# RC-SD2IEC_DJV.net
KiCad netlist of a schematic drawn in EAGLE
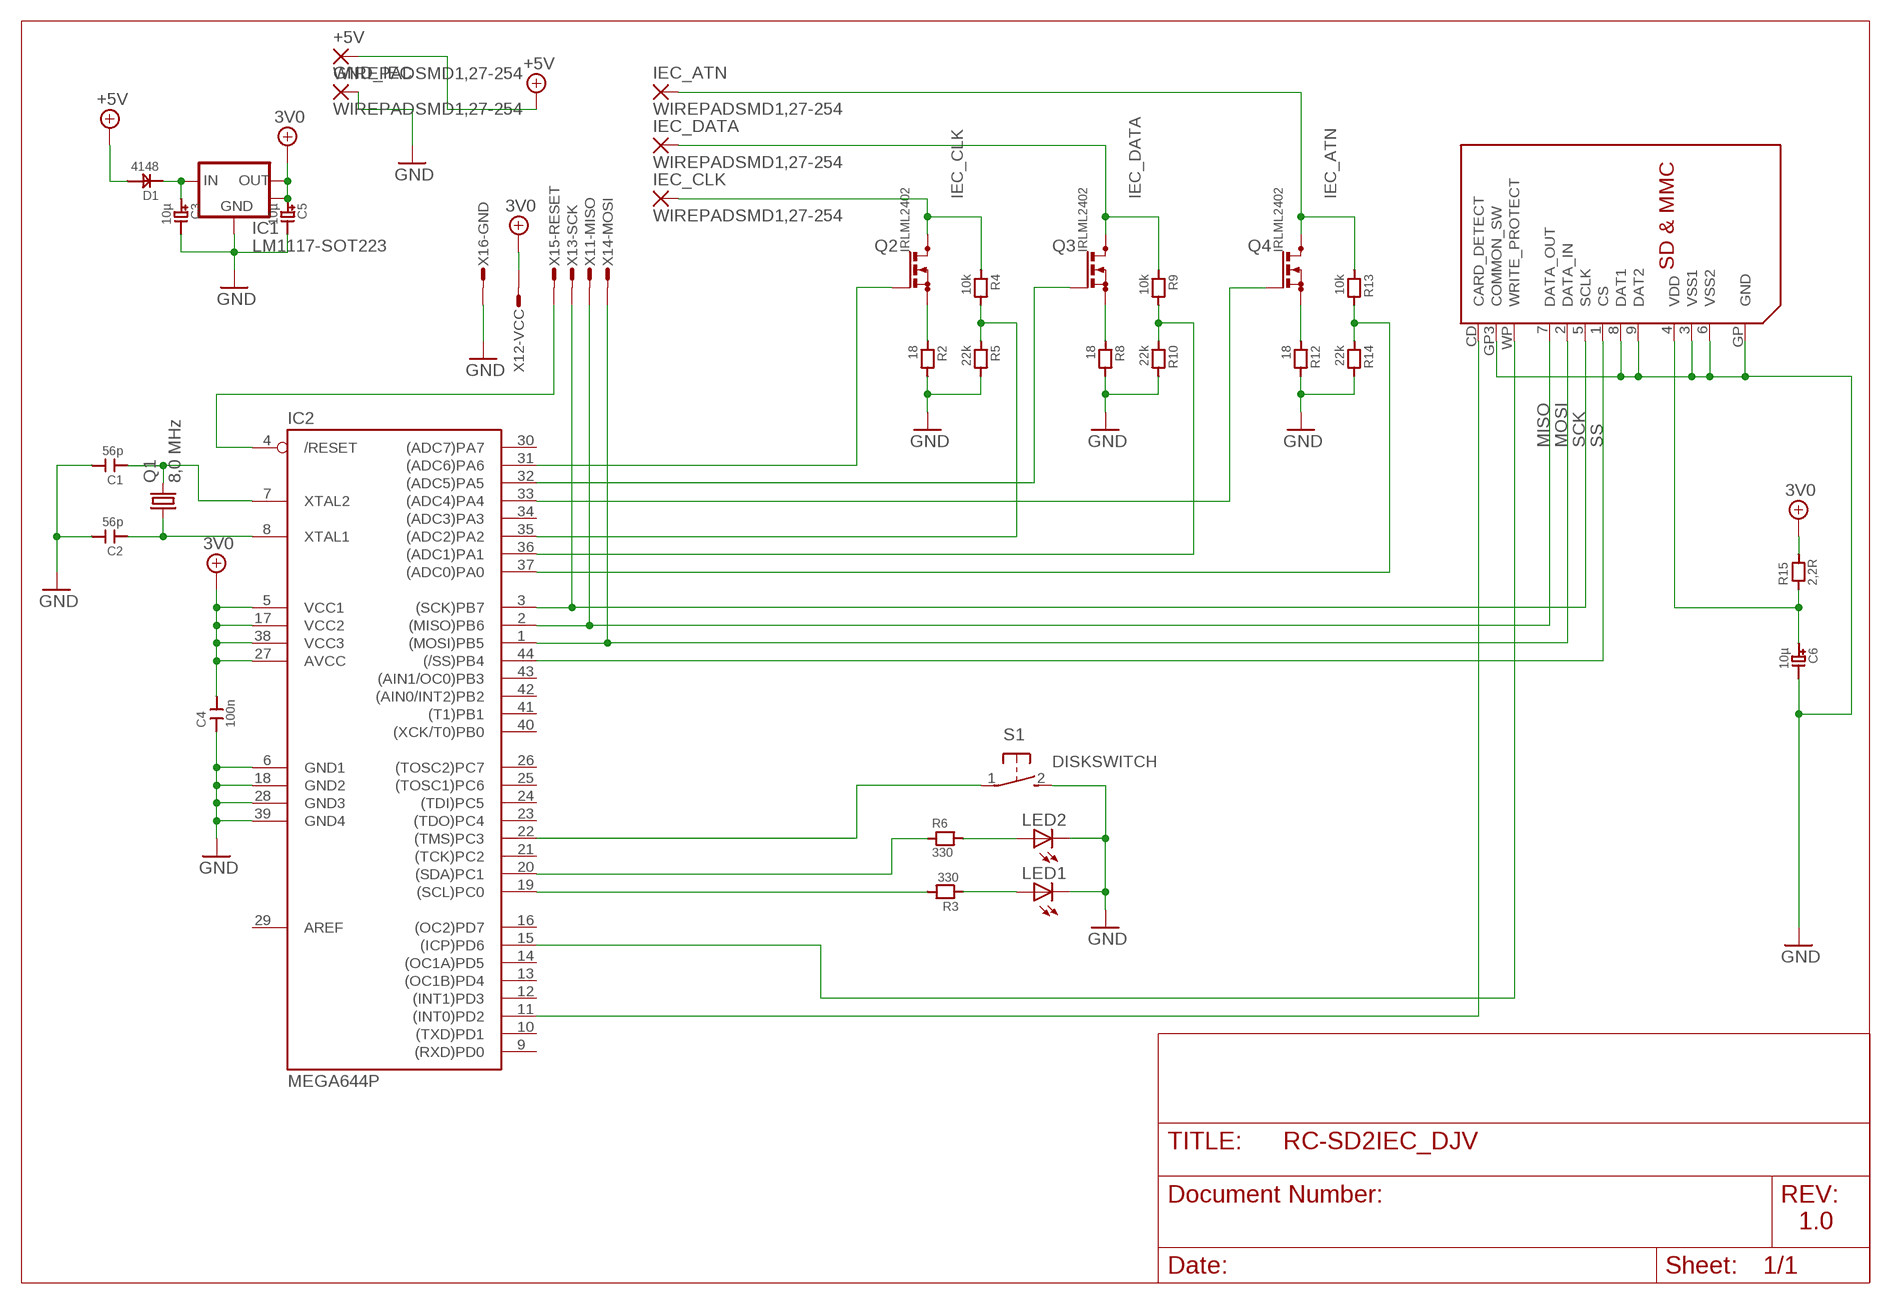
[diagram p0: schematic, sheet 1]

(export (version "E")
  (design (tool "Eeschema 10.0.6"))
  (components
    (comp (ref "+5V")
      (value "WIREPADSMD1,27-254")
      (footprint "eagle-import:SMD1,27-2,54")
      (libsource (lib "eagle-import") (part "WIREPADSMD1,27-254"))
    )
    (comp (ref "C1")
      (value "56p")
      (footprint "eagle-import:C0805")
      (libsource (lib "eagle-import") (part "C0805"))
    )
    (comp (ref "C2")
      (value "56p")
      (footprint "eagle-import:C0805")
      (libsource (lib "eagle-import") (part "C0805"))
    )
    (comp (ref "C3")
      (value "10µ")
      (footprint "eagle-import:C_TANTAL_A")
      (libsource (lib "eagle-import") (part "C_POLTA_A"))
    )
    (comp (ref "C4")
      (value "100n")
      (footprint "eagle-import:C1206")
      (libsource (lib "eagle-import") (part "C1206"))
    )
    (comp (ref "C5")
      (value "10µ")
      (footprint "eagle-import:C_TANTAL_A")
      (libsource (lib "eagle-import") (part "C_POLTA_A"))
    )
    (comp (ref "C6")
      (value "10µ")
      (footprint "eagle-import:C_TANTAL_A")
      (libsource (lib "eagle-import") (part "C_POLTA_A"))
    )
    (comp (ref "D1")
      (value "4148")
      (footprint "eagle-import:SOD-123")
      (libsource (lib "eagle-import") (part "DSOD-123"))
    )
    (comp (ref "GND_IEC")
      (value "WIREPADSMD1,27-254")
      (footprint "eagle-import:SMD1,27-2,54")
      (libsource (lib "eagle-import") (part "WIREPADSMD1,27-254"))
    )
    (comp (ref "IC1")
      (value "LM1117-SOT223")
      (footprint "eagle-import:SOT-223-3")
      (libsource (lib "eagle-import") (part "LM1117-SOT223"))
    )
    (comp (ref "IC2")
      (value "MEGA644P")
      (footprint "eagle-import:TQFP44")
      (libsource (lib "eagle-import") (part "MEGA16/32TQFP"))
    )
    (comp (ref "IEC_ATN")
      (value "WIREPADSMD1,27-254")
      (footprint "eagle-import:SMD1,27-2,54")
      (libsource (lib "eagle-import") (part "WIREPADSMD1,27-254"))
    )
    (comp (ref "IEC_CLK")
      (value "WIREPADSMD1,27-254")
      (footprint "eagle-import:SMD1,27-2,54")
      (libsource (lib "eagle-import") (part "WIREPADSMD1,27-254"))
    )
    (comp (ref "IEC_DATA")
      (value "WIREPADSMD1,27-254")
      (footprint "eagle-import:SMD1,27-2,54")
      (libsource (lib "eagle-import") (part "WIREPADSMD1,27-254"))
    )
    (comp (ref "LED1")
      (value "LED3MM")
      (footprint "eagle-import:LED3MM")
      (libsource (lib "eagle-import") (part "LED3MM"))
    )
    (comp (ref "LED2")
      (value "LED3MM")
      (footprint "eagle-import:LED3MM")
      (libsource (lib "eagle-import") (part "LED3MM"))
    )
    (comp (ref "Q1")
      (value "8,0 MHz")
      (footprint "eagle-import:CTS406")
      (libsource (lib "eagle-import") (part "CRYSTALCTS406"))
    )
    (comp (ref "Q2")
      (value "IRLML2402")
      (footprint "eagle-import:SOT23_C")
      (libsource (lib "eagle-import") (part "BSN20_C"))
    )
    (comp (ref "Q3")
      (value "IRLML2402")
      (footprint "eagle-import:SOT23_C")
      (libsource (lib "eagle-import") (part "BSN20_C"))
    )
    (comp (ref "Q4")
      (value "IRLML2402")
      (footprint "eagle-import:SOT23_C")
      (libsource (lib "eagle-import") (part "BSN20_C"))
    )
    (comp (ref "R2")
      (value "18")
      (footprint "eagle-import:R0805")
      (libsource (lib "eagle-import") (part "R0805"))
    )
    (comp (ref "R3")
      (value "330")
      (footprint "eagle-import:R0805")
      (libsource (lib "eagle-import") (part "R0805"))
    )
    (comp (ref "R4")
      (value "10k")
      (footprint "eagle-import:R0805")
      (libsource (lib "eagle-import") (part "R0805"))
    )
    (comp (ref "R5")
      (value "22k")
      (footprint "eagle-import:R0805")
      (libsource (lib "eagle-import") (part "R0805"))
    )
    (comp (ref "R6")
      (value "330")
      (footprint "eagle-import:R0805")
      (libsource (lib "eagle-import") (part "R0805"))
    )
    (comp (ref "R8")
      (value "18")
      (footprint "eagle-import:R0805")
      (libsource (lib "eagle-import") (part "R0805"))
    )
    (comp (ref "R9")
      (value "10k")
      (footprint "eagle-import:R0805")
      (libsource (lib "eagle-import") (part "R0805"))
    )
    (comp (ref "R10")
      (value "22k")
      (footprint "eagle-import:R0805")
      (libsource (lib "eagle-import") (part "R0805"))
    )
    (comp (ref "R12")
      (value "18")
      (footprint "eagle-import:R0805")
      (libsource (lib "eagle-import") (part "R0805"))
    )
    (comp (ref "R13")
      (value "10k")
      (footprint "eagle-import:R0805")
      (libsource (lib "eagle-import") (part "R0805"))
    )
    (comp (ref "R14")
      (value "22k")
      (footprint "eagle-import:R0805")
      (libsource (lib "eagle-import") (part "R0805"))
    )
    (comp (ref "R15")
      (value "2,2R")
      (footprint "eagle-import:R0805")
      (libsource (lib "eagle-import") (part "R0805"))
    )
    (comp (ref "S1")
      (value "31-XX")
      (footprint "eagle-import:B3F-31XX")
      (libsource (lib "eagle-import") (part "31-XX"))
    )
    (comp (ref "SDMMC1")
      (value "SDMMC06132")
      (footprint "eagle-import:06132")
      (libsource (lib "eagle-import") (part "SDMMC06132"))
    )
    (comp (ref "X1")
      (value "AVR-ISP_1X6")
      (footprint "eagle-import:1X6_ISP")
      (libsource (lib "eagle-import") (part "AVR-ISP_1X6"))
    )
  )
  (nets
    (net (code "1") (name "+5V") (class "Default")
      (node (ref "+5V") (pin "1") (pinfunction "P_1") (pintype "passive"))
      (node (ref "D1") (pin "2") (pinfunction "2_2") (pintype "passive"))
    )
    (net (code "2") (name "/DISKSWITCH") (class "Default")
      (node (ref "IC2") (pin "22") (pinfunction "(TMS)PC3_22") (pintype "bidirectional"))
      (node (ref "S1") (pin "1") (pinfunction "P_1") (pintype "passive"))
    )
    (net (code "3") (name "/IEC_ATN") (class "Default")
      (node (ref "IEC_ATN") (pin "1") (pinfunction "P_1") (pintype "passive"))
      (node (ref "Q4") (pin "3") (pinfunction "D_3") (pintype "passive"))
      (node (ref "R13") (pin "1") (pinfunction "1_1") (pintype "passive"))
    )
    (net (code "4") (name "/IEC_CLK") (class "Default")
      (node (ref "IEC_CLK") (pin "1") (pinfunction "P_1") (pintype "passive"))
      (node (ref "Q2") (pin "3") (pinfunction "D_3") (pintype "passive"))
      (node (ref "R4") (pin "1") (pinfunction "1_1") (pintype "passive"))
    )
    (net (code "5") (name "/IEC_DATA") (class "Default")
      (node (ref "IEC_DATA") (pin "1") (pinfunction "P_1") (pintype "passive"))
      (node (ref "Q3") (pin "3") (pinfunction "D_3") (pintype "passive"))
      (node (ref "R9") (pin "1") (pinfunction "1_1") (pintype "passive"))
    )
    (net (code "6") (name "/MISO") (class "Default")
      (node (ref "IC2") (pin "2") (pinfunction "(MISO)PB6_2") (pintype "bidirectional"))
      (node (ref "SDMMC1") (pin "7") (pinfunction "DATA_OUT_7") (pintype "output"))
      (node (ref "X1") (pin "1") (pinfunction "S_1") (pintype "passive"))
    )
    (net (code "7") (name "/MOSI") (class "Default")
      (node (ref "IC2") (pin "1") (pinfunction "(MOSI)PB5_1") (pintype "bidirectional"))
      (node (ref "SDMMC1") (pin "2") (pinfunction "DATA_IN_2") (pintype "input"))
      (node (ref "X1") (pin "4") (pinfunction "S_4") (pintype "passive"))
    )
    (net (code "8") (name "/SCK") (class "Default")
      (node (ref "IC2") (pin "3") (pinfunction "(SCK)PB7_3") (pintype "bidirectional"))
      (node (ref "SDMMC1") (pin "5") (pinfunction "SCLK_5") (pintype "input"))
      (node (ref "X1") (pin "3") (pinfunction "S_3") (pintype "passive"))
    )
    (net (code "9") (name "/SS") (class "Default")
      (node (ref "IC2") (pin "44") (pinfunction "(/SS)PB4_44") (pintype "bidirectional"))
      (node (ref "SDMMC1") (pin "1") (pinfunction "CS_1") (pintype "input"))
    )
    (net (code "10") (name "3V0") (class "Default")
      (node (ref "C4") (pin "2") (pinfunction "2_2") (pintype "passive"))
      (node (ref "C5") (pin "1") (pinfunction "1_1") (pintype "passive"))
      (node (ref "IC1") (pin "2") (pinfunction "VOUT_2") (pintype "bidirectional"))
      (node (ref "IC1") (pin "4") (pinfunction "HEATSINK_4") (pintype "bidirectional"))
      (node (ref "IC2") (pin "17") (pinfunction "VCC2_17") (pintype "power_in"))
      (node (ref "IC2") (pin "27") (pinfunction "AVCC_27") (pintype "power_in"))
      (node (ref "IC2") (pin "38") (pinfunction "VCC3_38") (pintype "power_in"))
      (node (ref "IC2") (pin "5") (pinfunction "VCC1_5") (pintype "power_in"))
      (node (ref "R15") (pin "2") (pinfunction "2_2") (pintype "passive"))
      (node (ref "X1") (pin "2") (pinfunction "S_2") (pintype "passive"))
    )
    (net (code "11") (name "GND") (class "Default")
      (node (ref "C1") (pin "2") (pinfunction "2_2") (pintype "passive"))
      (node (ref "C2") (pin "2") (pinfunction "2_2") (pintype "passive"))
      (node (ref "C3") (pin "2") (pinfunction "2_2") (pintype "passive"))
      (node (ref "C4") (pin "1") (pinfunction "1_1") (pintype "passive"))
      (node (ref "C5") (pin "2") (pinfunction "2_2") (pintype "passive"))
      (node (ref "C6") (pin "2") (pinfunction "2_2") (pintype "passive"))
      (node (ref "GND_IEC") (pin "1") (pinfunction "P_1") (pintype "passive"))
      (node (ref "IC1") (pin "1") (pinfunction "GND_1") (pintype "bidirectional"))
      (node (ref "IC2") (pin "18") (pinfunction "GND2_18") (pintype "power_in"))
      (node (ref "IC2") (pin "28") (pinfunction "GND3_28") (pintype "power_in"))
      (node (ref "IC2") (pin "39") (pinfunction "GND4_39") (pintype "power_in"))
      (node (ref "IC2") (pin "6") (pinfunction "GND1_6") (pintype "power_in"))
      (node (ref "LED1") (pin "K") (pinfunction "C_K") (pintype "passive"))
      (node (ref "LED2") (pin "K") (pinfunction "C_K") (pintype "passive"))
      (node (ref "R10") (pin "2") (pinfunction "2_2") (pintype "passive"))
      (node (ref "R12") (pin "2") (pinfunction "2_2") (pintype "passive"))
      (node (ref "R14") (pin "2") (pinfunction "2_2") (pintype "passive"))
      (node (ref "R2") (pin "2") (pinfunction "2_2") (pintype "passive"))
      (node (ref "R5") (pin "2") (pinfunction "2_2") (pintype "passive"))
      (node (ref "R8") (pin "2") (pinfunction "2_2") (pintype "passive"))
      (node (ref "S1") (pin "2") (pinfunction "S_2") (pintype "passive"))
      (node (ref "SDMMC1") (pin "3") (pinfunction "VSS1_3") (pintype "power_in"))
      (node (ref "SDMMC1") (pin "6") (pinfunction "VSS2_6") (pintype "power_in"))
      (node (ref "SDMMC1") (pin "8") (pinfunction "DAT1_8") (pintype "bidirectional"))
      (node (ref "SDMMC1") (pin "9") (pinfunction "DAT2_9") (pintype "bidirectional"))
      (node (ref "SDMMC1") (pin "GP") (pinfunction "GND_GP") (pintype "power_in"))
      (node (ref "SDMMC1") (pin "GP3") (pinfunction "COMMON_SW_GP3") (pintype "passive"))
      (node (ref "X1") (pin "6") (pinfunction "S_6") (pintype "passive"))
    )
    (net (code "12") (name "Net-(IC1-VIN)") (class "Default")
      (node (ref "C3") (pin "1") (pinfunction "1_1") (pintype "passive"))
      (node (ref "D1") (pin "1") (pinfunction "1_1") (pintype "passive"))
      (node (ref "IC1") (pin "3") (pinfunction "VIN_3") (pintype "bidirectional"))
    )
    (net (code "13") (name "Net-(IC2-(ADC0)PA0)") (class "Default")
      (node (ref "IC2") (pin "37") (pinfunction "(ADC0)PA0_37") (pintype "bidirectional"))
      (node (ref "R13") (pin "2") (pinfunction "2_2") (pintype "passive"))
      (node (ref "R14") (pin "1") (pinfunction "1_1") (pintype "passive"))
    )
    (net (code "14") (name "Net-(IC2-(ADC1)PA1)") (class "Default")
      (node (ref "IC2") (pin "36") (pinfunction "(ADC1)PA1_36") (pintype "bidirectional"))
      (node (ref "R10") (pin "1") (pinfunction "1_1") (pintype "passive"))
      (node (ref "R9") (pin "2") (pinfunction "2_2") (pintype "passive"))
    )
    (net (code "15") (name "Net-(IC2-(ADC2)PA2)") (class "Default")
      (node (ref "IC2") (pin "35") (pinfunction "(ADC2)PA2_35") (pintype "bidirectional"))
      (node (ref "R4") (pin "2") (pinfunction "2_2") (pintype "passive"))
      (node (ref "R5") (pin "1") (pinfunction "1_1") (pintype "passive"))
    )
    (net (code "16") (name "Net-(IC2-(ADC4)PA4)") (class "Default")
      (node (ref "IC2") (pin "33") (pinfunction "(ADC4)PA4_33") (pintype "bidirectional"))
      (node (ref "Q4") (pin "1") (pinfunction "G_1") (pintype "passive"))
    )
    (net (code "17") (name "Net-(IC2-(ADC5)PA5)") (class "Default")
      (node (ref "IC2") (pin "32") (pinfunction "(ADC5)PA5_32") (pintype "bidirectional"))
      (node (ref "Q3") (pin "1") (pinfunction "G_1") (pintype "passive"))
    )
    (net (code "18") (name "Net-(IC2-(ADC6)PA6)") (class "Default")
      (node (ref "IC2") (pin "31") (pinfunction "(ADC6)PA6_31") (pintype "bidirectional"))
      (node (ref "Q2") (pin "1") (pinfunction "G_1") (pintype "passive"))
    )
    (net (code "19") (name "Net-(IC2-(ICP)PD6)") (class "Default")
      (node (ref "IC2") (pin "15") (pinfunction "(ICP)PD6_15") (pintype "bidirectional"))
      (node (ref "SDMMC1") (pin "WP") (pinfunction "WRITE_PROTECT_WP") (pintype "passive"))
    )
    (net (code "20") (name "Net-(IC2-(INT0)PD2)") (class "Default")
      (node (ref "IC2") (pin "11") (pinfunction "(INT0)PD2_11") (pintype "bidirectional"))
      (node (ref "SDMMC1") (pin "CD") (pinfunction "CARD_DETECT_CD") (pintype "passive"))
    )
    (net (code "21") (name "Net-(IC2-(SCL)PC0)") (class "Default")
      (node (ref "IC2") (pin "19") (pinfunction "(SCL)PC0_19") (pintype "bidirectional"))
      (node (ref "R3") (pin "2") (pinfunction "2_2") (pintype "passive"))
    )
    (net (code "22") (name "Net-(IC2-(SDA)PC1)") (class "Default")
      (node (ref "IC2") (pin "20") (pinfunction "(SDA)PC1_20") (pintype "bidirectional"))
      (node (ref "R6") (pin "1") (pinfunction "1_1") (pintype "passive"))
    )
    (net (code "23") (name "Net-(IC2-XTAL1)") (class "Default")
      (node (ref "C2") (pin "1") (pinfunction "1_1") (pintype "passive"))
      (node (ref "IC2") (pin "8") (pinfunction "XTAL1_8") (pintype "input"))
      (node (ref "Q1") (pin "1") (pinfunction "1_1") (pintype "passive"))
    )
    (net (code "24") (name "Net-(IC2-XTAL2)") (class "Default")
      (node (ref "C1") (pin "1") (pinfunction "1_1") (pintype "passive"))
      (node (ref "IC2") (pin "7") (pinfunction "XTAL2_7") (pintype "input"))
      (node (ref "Q1") (pin "3") (pinfunction "2_3") (pintype "passive"))
    )
    (net (code "25") (name "Net-(IC2-{slash}RESET)") (class "Default")
      (node (ref "IC2") (pin "4") (pinfunction "/RESET_4") (pintype "input"))
      (node (ref "X1") (pin "5") (pinfunction "S_5") (pintype "passive"))
    )
    (net (code "26") (name "Net-(LED1-PadA)") (class "Default")
      (node (ref "LED1") (pin "A") (pinfunction "A_A") (pintype "passive"))
      (node (ref "R3") (pin "1") (pinfunction "1_1") (pintype "passive"))
    )
    (net (code "27") (name "Net-(LED2-PadA)") (class "Default")
      (node (ref "LED2") (pin "A") (pinfunction "A_A") (pintype "passive"))
      (node (ref "R6") (pin "2") (pinfunction "2_2") (pintype "passive"))
    )
    (net (code "28") (name "Net-(Q2-S)") (class "Default")
      (node (ref "Q2") (pin "2") (pinfunction "S_2") (pintype "passive"))
      (node (ref "R2") (pin "1") (pinfunction "1_1") (pintype "passive"))
    )
    (net (code "29") (name "Net-(Q3-S)") (class "Default")
      (node (ref "Q3") (pin "2") (pinfunction "S_2") (pintype "passive"))
      (node (ref "R8") (pin "1") (pinfunction "1_1") (pintype "passive"))
    )
    (net (code "30") (name "Net-(Q4-S)") (class "Default")
      (node (ref "Q4") (pin "2") (pinfunction "S_2") (pintype "passive"))
      (node (ref "R12") (pin "1") (pinfunction "1_1") (pintype "passive"))
    )
    (net (code "31") (name "Net-(SDMMC1-VDD)") (class "Default")
      (node (ref "C6") (pin "1") (pinfunction "1_1") (pintype "passive"))
      (node (ref "R15") (pin "1") (pinfunction "1_1") (pintype "passive"))
      (node (ref "SDMMC1") (pin "4") (pinfunction "VDD_4") (pintype "power_in"))
    )
    (net (code "32") (name "unconnected-(IC2-(ADC3)PA3-Pad34)") (class "Default")
      (node (ref "IC2") (pin "34") (pinfunction "(ADC3)PA3_34") (pintype "bidirectional"))
    )
    (net (code "33") (name "unconnected-(IC2-(ADC7)PA7-Pad30)") (class "Default")
      (node (ref "IC2") (pin "30") (pinfunction "(ADC7)PA7_30") (pintype "bidirectional"))
    )
    (net (code "34") (name "unconnected-(IC2-(AIN0{slash}INT2)PB2-Pad42)") (class "Default")
      (node (ref "IC2") (pin "42") (pinfunction "(AIN0/INT2)PB2_42") (pintype "bidirectional"))
    )
    (net (code "35") (name "unconnected-(IC2-(AIN1{slash}OC0)PB3-Pad43)") (class "Default")
      (node (ref "IC2") (pin "43") (pinfunction "(AIN1/OC0)PB3_43") (pintype "bidirectional"))
    )
    (net (code "36") (name "unconnected-(IC2-(INT1)PD3-Pad12)") (class "Default")
      (node (ref "IC2") (pin "12") (pinfunction "(INT1)PD3_12") (pintype "bidirectional"))
    )
    (net (code "37") (name "unconnected-(IC2-(OC1A)PD5-Pad14)") (class "Default")
      (node (ref "IC2") (pin "14") (pinfunction "(OC1A)PD5_14") (pintype "bidirectional"))
    )
    (net (code "38") (name "unconnected-(IC2-(OC1B)PD4-Pad13)") (class "Default")
      (node (ref "IC2") (pin "13") (pinfunction "(OC1B)PD4_13") (pintype "bidirectional"))
    )
    (net (code "39") (name "unconnected-(IC2-(OC2)PD7-Pad16)") (class "Default")
      (node (ref "IC2") (pin "16") (pinfunction "(OC2)PD7_16") (pintype "bidirectional"))
    )
    (net (code "40") (name "unconnected-(IC2-(RXD)PD0-Pad9)") (class "Default")
      (node (ref "IC2") (pin "9") (pinfunction "(RXD)PD0_9") (pintype "bidirectional"))
    )
    (net (code "41") (name "unconnected-(IC2-(T1)PB1-Pad41)") (class "Default")
      (node (ref "IC2") (pin "41") (pinfunction "(T1)PB1_41") (pintype "bidirectional"))
    )
    (net (code "42") (name "unconnected-(IC2-(TCK)PC2-Pad21)") (class "Default")
      (node (ref "IC2") (pin "21") (pinfunction "(TCK)PC2_21") (pintype "bidirectional"))
    )
    (net (code "43") (name "unconnected-(IC2-(TDI)PC5-Pad24)") (class "Default")
      (node (ref "IC2") (pin "24") (pinfunction "(TDI)PC5_24") (pintype "bidirectional"))
    )
    (net (code "44") (name "unconnected-(IC2-(TDO)PC4-Pad23)") (class "Default")
      (node (ref "IC2") (pin "23") (pinfunction "(TDO)PC4_23") (pintype "bidirectional"))
    )
    (net (code "45") (name "unconnected-(IC2-(TOSC1)PC6-Pad25)") (class "Default")
      (node (ref "IC2") (pin "25") (pinfunction "(TOSC1)PC6_25") (pintype "bidirectional"))
    )
    (net (code "46") (name "unconnected-(IC2-(TOSC2)PC7-Pad26)") (class "Default")
      (node (ref "IC2") (pin "26") (pinfunction "(TOSC2)PC7_26") (pintype "bidirectional"))
    )
    (net (code "47") (name "unconnected-(IC2-(TXD)PD1-Pad10)") (class "Default")
      (node (ref "IC2") (pin "10") (pinfunction "(TXD)PD1_10") (pintype "bidirectional"))
    )
    (net (code "48") (name "unconnected-(IC2-(XCK{slash}T0)PB0-Pad40)") (class "Default")
      (node (ref "IC2") (pin "40") (pinfunction "(XCK/T0)PB0_40") (pintype "bidirectional"))
    )
    (net (code "49") (name "unconnected-(IC2-AREF-Pad29)") (class "Default")
      (node (ref "IC2") (pin "29") (pinfunction "AREF_29") (pintype "bidirectional"))
    )
  )
)
